# SH4_-_Level_Shifter.net
KiCad netlist of a schematic drawn in Altium Designer
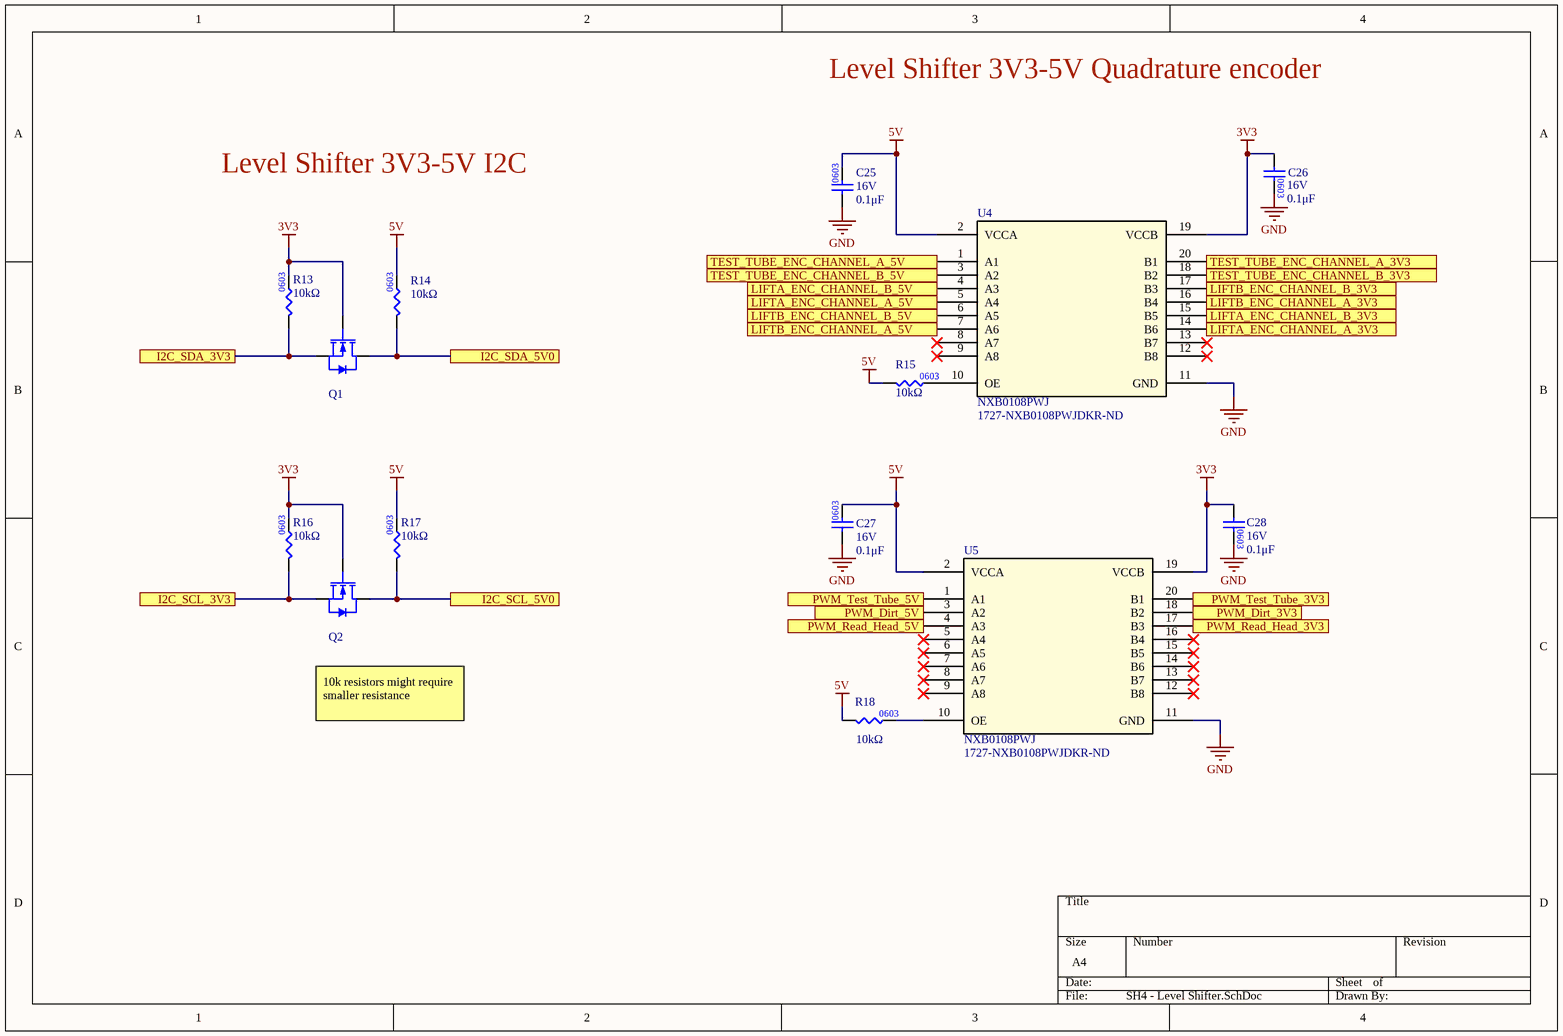
[diagram p0: SH4 - Level Shifter.SchDoc]

(export (version "E")
  (design (tool "Eeschema 10.0.6"))
  (components
    (comp (ref "C25")
      (value "0.1μF")
      (footprint "CAP0603")
      (description "CAP CER 0.1UF 16V X7R 0603")
      (fields (field (name "VOLTAGE RATING") "16V") (field (name "Comment") "CAP_0.1uF_16V_0603"))
      (libsource (lib "UWRT_Schematic_Library_2020") (part "CAP_0.1uF_16V_0603"))
    )
    (comp (ref "C26")
      (value "0.1μF")
      (footprint "CAP0603")
      (description "CAP CER 0.1UF 16V X7R 0603")
      (fields (field (name "VOLTAGE RATING") "16V") (field (name "Comment") "CAP_0.1uF_16V_0603"))
      (libsource (lib "UWRT_Schematic_Library_2020") (part "CAP_0.1uF_16V_0603"))
    )
    (comp (ref "C27")
      (value "0.1μF")
      (footprint "CAP0603")
      (description "CAP CER 0.1UF 16V X7R 0603")
      (fields (field (name "VOLTAGE RATING") "16V") (field (name "Comment") "CAP_0.1uF_16V_0603"))
      (libsource (lib "UWRT_Schematic_Library_2020") (part "CAP_0.1uF_16V_0603"))
    )
    (comp (ref "C28")
      (value "0.1μF")
      (footprint "CAP0603")
      (description "CAP CER 0.1UF 16V X7R 0603")
      (fields (field (name "VOLTAGE RATING") "16V") (field (name "Comment") "CAP_0.1uF_16V_0603"))
      (libsource (lib "UWRT_Schematic_Library_2020") (part "CAP_0.1uF_16V_0603"))
    )
    (comp (ref "Q1")
      (value "NMOS_60V_280mA")
      (footprint "SOT-323")
      (description "MOSFET N-CH 60V 280MA SOT323-3")
      (libsource (lib "UWRT_Schematic_Library_2020") (part "NMOS_60V_280mA"))
    )
    (comp (ref "Q2")
      (value "NMOS_60V_280mA")
      (footprint "SOT-323")
      (description "MOSFET N-CH 60V 280MA SOT323-3")
      (libsource (lib "UWRT_Schematic_Library_2020") (part "NMOS_60V_280mA"))
    )
    (comp (ref "R13")
      (value "10kΩ")
      (footprint "RES0603")
      (description "RES 10K OHM 5% 1/10W 0603")
      (fields (field (name "Comment") "RES_10kΩ_0603_5%"))
      (libsource (lib "UWRT_Schematic_Library_2020") (part "RES_10kΩ_0603_5%"))
    )
    (comp (ref "R14")
      (value "10kΩ")
      (footprint "RES0603")
      (description "RES 10K OHM 5% 1/10W 0603")
      (fields (field (name "Comment") "RES_10kΩ_0603_5%"))
      (libsource (lib "UWRT_Schematic_Library_2020") (part "RES_10kΩ_0603_5%"))
    )
    (comp (ref "R15")
      (value "10kΩ")
      (footprint "RES0603")
      (description "RES 10K OHM 5% 1/10W 0603")
      (fields (field (name "Comment") "RES_10kΩ_0603_5%"))
      (libsource (lib "UWRT_Schematic_Library_2020") (part "RES_10kΩ_0603_5%"))
    )
    (comp (ref "R16")
      (value "10kΩ")
      (footprint "RES0603")
      (description "RES 10K OHM 5% 1/10W 0603")
      (fields (field (name "Comment") "RES_10kΩ_0603_5%"))
      (libsource (lib "UWRT_Schematic_Library_2020") (part "RES_10kΩ_0603_5%"))
    )
    (comp (ref "R17")
      (value "10kΩ")
      (footprint "RES0603")
      (description "RES 10K OHM 5% 1/10W 0603")
      (fields (field (name "Comment") "RES_10kΩ_0603_5%"))
      (libsource (lib "UWRT_Schematic_Library_2020") (part "RES_10kΩ_0603_5%"))
    )
    (comp (ref "R18")
      (value "10kΩ")
      (footprint "RES0603")
      (description "RES 10K OHM 5% 1/10W 0603")
      (fields (field (name "Comment") "RES_10kΩ_0603_5%"))
      (libsource (lib "UWRT_Schematic_Library_2020") (part "RES_10kΩ_0603_5%"))
    )
    (comp (ref "U4")
      (value "IC_LVL_SHIFTER_8_CH")
      (footprint "LEVEL_SHIFTER_8_CHANNEL")
      (description "IC BIDIRECTIONAL LEVEL SHIFTER 8 CHANNEL 20TSSOP NEXPERIA")
      (fields
        (field (name "MANUFACTURER PART NUMBER 1") "NXB0108PWJ")
        (field (name "SUPPLIER PART NUMBER 1") "1727-NXB0108PWJDKR-ND")
      )
      (libsource (lib "UWRT_Schematic_Library_2020") (part "IC_LVL_SHIFTER_8_CH_NEXPERIA"))
    )
    (comp (ref "U5")
      (value "IC_LVL_SHIFTER_8_CH")
      (footprint "LEVEL_SHIFTER_8_CHANNEL")
      (description "IC BIDIRECTIONAL LEVEL SHIFTER 8 CHANNEL 20TSSOP NEXPERIA")
      (fields
        (field (name "MANUFACTURER PART NUMBER 1") "NXB0108PWJ")
        (field (name "SUPPLIER PART NUMBER 1") "1727-NXB0108PWJDKR-ND")
      )
      (libsource (lib "UWRT_Schematic_Library_2020") (part "IC_LVL_SHIFTER_8_CH_NEXPERIA"))
    )
  )
  (nets
    (net (code "1") (name "/I2C_SCL_3V3") (class "Default")
      (node (ref "Q2") (pin "2") (pinfunction "Source_2") (pintype "passive"))
      (node (ref "R16") (pin "1") (pinfunction "1_1") (pintype "passive"))
    )
    (net (code "2") (name "/I2C_SCL_5V0") (class "Default")
      (node (ref "Q2") (pin "3") (pinfunction "Drain_3") (pintype "passive"))
      (node (ref "R17") (pin "1") (pinfunction "1_1") (pintype "passive"))
    )
    (net (code "3") (name "/I2C_SDA_3V3") (class "Default")
      (node (ref "Q1") (pin "2") (pinfunction "Source_2") (pintype "passive"))
      (node (ref "R13") (pin "1") (pinfunction "1_1") (pintype "passive"))
    )
    (net (code "4") (name "/I2C_SDA_5V0") (class "Default")
      (node (ref "Q1") (pin "3") (pinfunction "Drain_3") (pintype "passive"))
      (node (ref "R14") (pin "1") (pinfunction "1_1") (pintype "passive"))
    )
    (net (code "5") (name "/LIFTA_ENC_CHANNEL_A_3V3") (class "Default")
      (node (ref "U4") (pin "14") (pinfunction "B6_14") (pintype "passive"))
    )
    (net (code "6") (name "/LIFTA_ENC_CHANNEL_A_5V") (class "Default")
      (node (ref "U4") (pin "5") (pinfunction "A4_5") (pintype "passive"))
    )
    (net (code "7") (name "/LIFTA_ENC_CHANNEL_B_3V3") (class "Default")
      (node (ref "U4") (pin "15") (pinfunction "B5_15") (pintype "passive"))
    )
    (net (code "8") (name "/LIFTA_ENC_CHANNEL_B_5V") (class "Default")
      (node (ref "U4") (pin "4") (pinfunction "A3_4") (pintype "passive"))
    )
    (net (code "9") (name "/LIFTB_ENC_CHANNEL_A_3V3") (class "Default")
      (node (ref "U4") (pin "16") (pinfunction "B4_16") (pintype "passive"))
    )
    (net (code "10") (name "/LIFTB_ENC_CHANNEL_A_5V") (class "Default")
      (node (ref "U4") (pin "7") (pinfunction "A6_7") (pintype "passive"))
    )
    (net (code "11") (name "/LIFTB_ENC_CHANNEL_B_3V3") (class "Default")
      (node (ref "U4") (pin "17") (pinfunction "B3_17") (pintype "passive"))
    )
    (net (code "12") (name "/LIFTB_ENC_CHANNEL_B_5V") (class "Default")
      (node (ref "U4") (pin "6") (pinfunction "A5_6") (pintype "passive"))
    )
    (net (code "13") (name "/PWM_Dirt_3V3") (class "Default")
      (node (ref "U5") (pin "18") (pinfunction "B2_18") (pintype "passive"))
    )
    (net (code "14") (name "/PWM_Dirt_5V") (class "Default")
      (node (ref "U5") (pin "3") (pinfunction "A2_3") (pintype "passive"))
    )
    (net (code "15") (name "/PWM_Read_Head_3V3") (class "Default")
      (node (ref "U5") (pin "17") (pinfunction "B3_17") (pintype "passive"))
    )
    (net (code "16") (name "/PWM_Read_Head_5V") (class "Default")
      (node (ref "U5") (pin "4") (pinfunction "A3_4") (pintype "passive"))
    )
    (net (code "17") (name "/PWM_Test_Tube_3V3") (class "Default")
      (node (ref "U5") (pin "20") (pinfunction "B1_20") (pintype "passive"))
    )
    (net (code "18") (name "/PWM_Test_Tube_5V") (class "Default")
      (node (ref "U5") (pin "1") (pinfunction "A1_1") (pintype "passive"))
    )
    (net (code "19") (name "/TEST_TUBE_ENC_CHANNEL_A_3V3") (class "Default")
      (node (ref "U4") (pin "20") (pinfunction "B1_20") (pintype "passive"))
    )
    (net (code "20") (name "/TEST_TUBE_ENC_CHANNEL_A_5V") (class "Default")
      (node (ref "U4") (pin "1") (pinfunction "A1_1") (pintype "passive"))
    )
    (net (code "21") (name "/TEST_TUBE_ENC_CHANNEL_B_3V3") (class "Default")
      (node (ref "U4") (pin "18") (pinfunction "B2_18") (pintype "passive"))
    )
    (net (code "22") (name "/TEST_TUBE_ENC_CHANNEL_B_5V") (class "Default")
      (node (ref "U4") (pin "3") (pinfunction "A2_3") (pintype "passive"))
    )
    (net (code "23") (name "3V3") (class "Default")
      (node (ref "C26") (pin "1") (pinfunction "1_1") (pintype "passive"))
      (node (ref "C28") (pin "1") (pinfunction "1_1") (pintype "passive"))
      (node (ref "Q1") (pin "1") (pinfunction "Gate_1") (pintype "passive"))
      (node (ref "Q2") (pin "1") (pinfunction "Gate_1") (pintype "passive"))
      (node (ref "R13") (pin "2") (pinfunction "2_2") (pintype "passive"))
      (node (ref "R16") (pin "2") (pinfunction "2_2") (pintype "passive"))
      (node (ref "U4") (pin "19") (pinfunction "VCCB_19") (pintype "passive"))
      (node (ref "U5") (pin "19") (pinfunction "VCCB_19") (pintype "passive"))
    )
    (net (code "24") (name "5V") (class "Default")
      (node (ref "C25") (pin "2") (pinfunction "2_2") (pintype "passive"))
      (node (ref "C27") (pin "2") (pinfunction "2_2") (pintype "passive"))
      (node (ref "R14") (pin "2") (pinfunction "2_2") (pintype "passive"))
      (node (ref "R15") (pin "1") (pinfunction "1_1") (pintype "passive"))
      (node (ref "R17") (pin "2") (pinfunction "2_2") (pintype "passive"))
      (node (ref "R18") (pin "1") (pinfunction "1_1") (pintype "passive"))
      (node (ref "U4") (pin "2") (pinfunction "VCCA_2") (pintype "passive"))
      (node (ref "U5") (pin "2") (pinfunction "VCCA_2") (pintype "passive"))
    )
    (net (code "25") (name "GND") (class "Default")
      (node (ref "C25") (pin "1") (pinfunction "1_1") (pintype "passive"))
      (node (ref "C26") (pin "2") (pinfunction "2_2") (pintype "passive"))
      (node (ref "C27") (pin "1") (pinfunction "1_1") (pintype "passive"))
      (node (ref "C28") (pin "2") (pinfunction "2_2") (pintype "passive"))
      (node (ref "U4") (pin "11") (pinfunction "GND_11") (pintype "passive"))
      (node (ref "U5") (pin "11") (pinfunction "GND_11") (pintype "passive"))
    )
    (net (code "26") (name "Net-(U4-OE)") (class "Default")
      (node (ref "R15") (pin "2") (pinfunction "2_2") (pintype "passive"))
      (node (ref "U4") (pin "10") (pinfunction "OE_10") (pintype "passive"))
    )
    (net (code "27") (name "Net-(U5-OE)") (class "Default")
      (node (ref "R18") (pin "2") (pinfunction "2_2") (pintype "passive"))
      (node (ref "U5") (pin "10") (pinfunction "OE_10") (pintype "passive"))
    )
    (net (code "28") (name "unconnected-(U4-A7-Pad8)") (class "Default")
      (node (ref "U4") (pin "8") (pinfunction "A7_8") (pintype "passive+no_connect"))
    )
    (net (code "29") (name "unconnected-(U4-A8-Pad9)") (class "Default")
      (node (ref "U4") (pin "9") (pinfunction "A8_9") (pintype "passive+no_connect"))
    )
    (net (code "30") (name "unconnected-(U4-B7-Pad13)") (class "Default")
      (node (ref "U4") (pin "13") (pinfunction "B7_13") (pintype "passive+no_connect"))
    )
    (net (code "31") (name "unconnected-(U4-B8-Pad12)") (class "Default")
      (node (ref "U4") (pin "12") (pinfunction "B8_12") (pintype "passive+no_connect"))
    )
    (net (code "32") (name "unconnected-(U5-A4-Pad5)") (class "Default")
      (node (ref "U5") (pin "5") (pinfunction "A4_5") (pintype "passive+no_connect"))
    )
    (net (code "33") (name "unconnected-(U5-A5-Pad6)") (class "Default")
      (node (ref "U5") (pin "6") (pinfunction "A5_6") (pintype "passive+no_connect"))
    )
    (net (code "34") (name "unconnected-(U5-A6-Pad7)") (class "Default")
      (node (ref "U5") (pin "7") (pinfunction "A6_7") (pintype "passive+no_connect"))
    )
    (net (code "35") (name "unconnected-(U5-A7-Pad8)") (class "Default")
      (node (ref "U5") (pin "8") (pinfunction "A7_8") (pintype "passive+no_connect"))
    )
    (net (code "36") (name "unconnected-(U5-A8-Pad9)") (class "Default")
      (node (ref "U5") (pin "9") (pinfunction "A8_9") (pintype "passive+no_connect"))
    )
    (net (code "37") (name "unconnected-(U5-B4-Pad16)") (class "Default")
      (node (ref "U5") (pin "16") (pinfunction "B4_16") (pintype "passive+no_connect"))
    )
    (net (code "38") (name "unconnected-(U5-B5-Pad15)") (class "Default")
      (node (ref "U5") (pin "15") (pinfunction "B5_15") (pintype "passive+no_connect"))
    )
    (net (code "39") (name "unconnected-(U5-B6-Pad14)") (class "Default")
      (node (ref "U5") (pin "14") (pinfunction "B6_14") (pintype "passive+no_connect"))
    )
    (net (code "40") (name "unconnected-(U5-B7-Pad13)") (class "Default")
      (node (ref "U5") (pin "13") (pinfunction "B7_13") (pintype "passive+no_connect"))
    )
    (net (code "41") (name "unconnected-(U5-B8-Pad12)") (class "Default")
      (node (ref "U5") (pin "12") (pinfunction "B8_12") (pintype "passive+no_connect"))
    )
  )
)
